# Power.net
KiCad netlist of a schematic drawn in Altium Designer
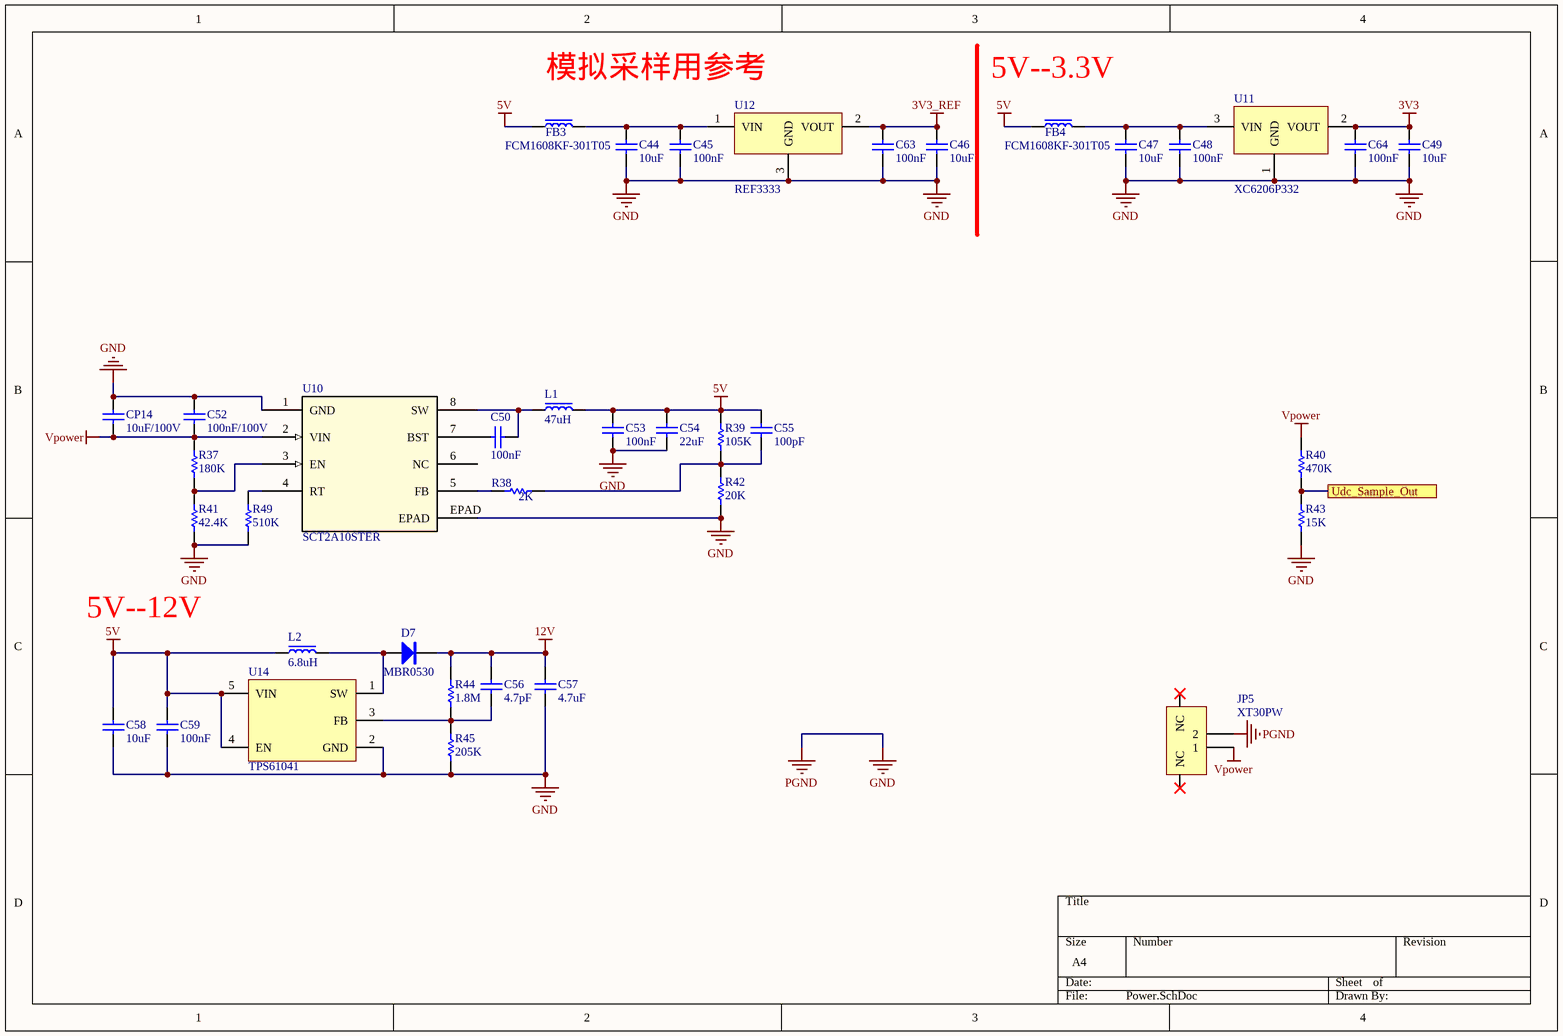
[diagram p0: Power.SchDoc]

(export (version "E")
  (design (tool "Eeschema 10.0.6"))
  (components
    (comp (ref "C44") (value "10uF") (footprint "C0603") (libsource (lib "Cap") (part "Cap")))
    (comp (ref "C45") (value "100nF") (footprint "C0603") (libsource (lib "Cap") (part "Cap")))
    (comp (ref "C46") (value "10uF") (footprint "C0603") (libsource (lib "Cap") (part "Cap")))
    (comp (ref "C47") (value "10uF") (footprint "C0603") (libsource (lib "Cap") (part "Cap")))
    (comp (ref "C48") (value "100nF") (footprint "C0603") (libsource (lib "Cap") (part "Cap")))
    (comp (ref "C49") (value "10uF") (footprint "C0603") (libsource (lib "Cap") (part "Cap")))
    (comp (ref "C50") (value "100nF") (footprint "C0603") (libsource (lib "Cap") (part "Cap")))
    (comp (ref "C52") (value "100nF/100V") (footprint "C0603") (libsource (lib "Cap") (part "Cap")))
    (comp (ref "C53") (value "100nF") (footprint "C0603") (libsource (lib "Cap") (part "Cap")))
    (comp (ref "C54") (value "22uF") (footprint "C0805") (libsource (lib "Cap") (part "Cap")))
    (comp (ref "C55") (value "100pF") (footprint "C0603") (libsource (lib "Cap") (part "Cap")))
    (comp (ref "C56") (value "4.7pF") (footprint "C0603") (libsource (lib "Cap") (part "Cap")))
    (comp (ref "C57") (value "4.7uF") (footprint "C0805") (libsource (lib "Cap") (part "Cap")))
    (comp (ref "C58") (value "10uF") (footprint "C0805") (libsource (lib "Cap") (part "Cap")))
    (comp (ref "C59") (value "100nF") (footprint "C0603") (libsource (lib "Cap") (part "Cap")))
    (comp (ref "C63") (value "100nF") (footprint "C0603") (libsource (lib "Cap") (part "Cap")))
    (comp (ref "C64") (value "100nF") (footprint "C0603") (libsource (lib "Cap") (part "Cap")))
    (comp (ref "CP14") (value "10uF/100V") (footprint "C1206") (libsource (lib "Cap") (part "Cap")))
    (comp (ref "D7")
      (value "MBR0530")
      (footprint "SOD-123")
      (description "30V 0.5A")
      (libsource (lib "All lib") (part "MBR0530"))
    )
    (comp (ref "FB3")
      (value "FCM1608KF-301T05")
      (footprint "FB 0402")
      (description "磁珠")
      (libsource (lib "All lib") (part "FB"))
    )
    (comp (ref "FB4")
      (value "FCM1608KF-301T05")
      (footprint "FB 0402")
      (description "磁珠")
      (libsource (lib "All lib") (part "FB"))
    )
    (comp (ref "JP5") (value "XT30PW") (footprint "XT30PW-M") (libsource (lib "All lib") (part "XT30PW")))
    (comp (ref "L1")
      (value "47uH")
      (footprint "L 0630")
      (description "功率屏蔽电感")
      (libsource (lib "All lib") (part "L-CDRH"))
    )
    (comp (ref "L2")
      (value "6.8uH")
      (footprint "L 0530")
      (description "功率屏蔽电感")
      (libsource (lib "All lib") (part "L-CDRH"))
    )
    (comp (ref "R37") (value "180K") (footprint "R0603") (libsource (lib "Res") (part "RES")))
    (comp (ref "R38") (value "2K") (footprint "R0603") (libsource (lib "Res") (part "RES")))
    (comp (ref "R39") (value "105K") (footprint "R0603") (libsource (lib "Res") (part "RES")))
    (comp (ref "R40") (value "470K") (footprint "R0402") (libsource (lib "Res") (part "RES")))
    (comp (ref "R41") (value "42.4K") (footprint "R0603") (libsource (lib "Res") (part "RES")))
    (comp (ref "R42") (value "20K") (footprint "R0603") (libsource (lib "Res") (part "RES")))
    (comp (ref "R43") (value "15K") (footprint "R0402") (libsource (lib "Res") (part "RES")))
    (comp (ref "R44") (value "1.8M") (footprint "R0603") (libsource (lib "Res") (part "RES")))
    (comp (ref "R45") (value "205K") (footprint "R0603") (libsource (lib "Res") (part "RES")))
    (comp (ref "R49") (value "510K") (footprint "R0603") (libsource (lib "Res") (part "RES")))
    (comp (ref "U10")
      (value "SCT2A10STER")
      (footprint "DDA8_3P1X2P41-L")
      (description "No Description Available")
      (libsource (lib "All lib") (part "SCT2A10STER"))
    )
    (comp (ref "U11")
      (value "XC6206P332")
      (footprint "SOT23-3L")
      (description "VIN < 6V")
      (libsource (lib "All lib") (part "XC6206"))
    )
    (comp (ref "U12")
      (value "REF3333")
      (footprint "SOT23-3L")
      (description "TI 电压基准")
      (libsource (lib "All lib") (part "REF33XX"))
    )
    (comp (ref "U14")
      (value "TPS61041")
      (footprint "SOT23-5L")
      (description "Boost DC-DC")
      (libsource (lib "All lib") (part "TPS6104x"))
    )
  )
  (nets
    (net (code "1") (name "/Udc_Sample_Out") (class "Default")
      (node (ref "R40") (pin "1") (pinfunction "1_1") (pintype "passive"))
      (node (ref "R43") (pin "2") (pinfunction "2_2") (pintype "passive"))
    )
    (net (code "2") (name "3V3") (class "Default")
      (node (ref "C49") (pin "2") (pinfunction "2_2") (pintype "passive"))
      (node (ref "C64") (pin "2") (pinfunction "2_2") (pintype "passive"))
      (node (ref "U11") (pin "2") (pinfunction "VOUT_2") (pintype "passive"))
    )
    (net (code "3") (name "3V3_REF") (class "Default")
      (node (ref "C46") (pin "2") (pinfunction "2_2") (pintype "passive"))
      (node (ref "C63") (pin "2") (pinfunction "2_2") (pintype "passive"))
      (node (ref "U12") (pin "2") (pinfunction "VOUT_2") (pintype "passive"))
    )
    (net (code "4") (name "5V") (class "Default")
      (node (ref "C53") (pin "2") (pinfunction "2_2") (pintype "passive"))
      (node (ref "C54") (pin "1") (pinfunction "1_1") (pintype "passive"))
      (node (ref "C55") (pin "1") (pinfunction "1_1") (pintype "passive"))
      (node (ref "C58") (pin "2") (pinfunction "2_2") (pintype "passive"))
      (node (ref "C59") (pin "2") (pinfunction "2_2") (pintype "passive"))
      (node (ref "FB3") (pin "1") (pinfunction "1_1") (pintype "passive"))
      (node (ref "FB4") (pin "1") (pinfunction "1_1") (pintype "passive"))
      (node (ref "L1") (pin "2") (pinfunction "2_2") (pintype "passive"))
      (node (ref "L2") (pin "1") (pinfunction "1_1") (pintype "passive"))
      (node (ref "R39") (pin "2") (pinfunction "2_2") (pintype "passive"))
      (node (ref "U14") (pin "4") (pinfunction "EN_4") (pintype "passive"))
      (node (ref "U14") (pin "5") (pinfunction "VIN_5") (pintype "passive"))
    )
    (net (code "5") (name "12V") (class "Default")
      (node (ref "C56") (pin "2") (pinfunction "2_2") (pintype "passive"))
      (node (ref "C57") (pin "2") (pinfunction "2_2") (pintype "passive"))
      (node (ref "D7") (pin "K") (pinfunction "K_K") (pintype "passive"))
      (node (ref "R44") (pin "1") (pinfunction "1_1") (pintype "passive"))
    )
    (net (code "6") (name "GND") (class "Default")
      (node (ref "C44") (pin "1") (pinfunction "1_1") (pintype "passive"))
      (node (ref "C45") (pin "1") (pinfunction "1_1") (pintype "passive"))
      (node (ref "C46") (pin "1") (pinfunction "1_1") (pintype "passive"))
      (node (ref "C47") (pin "1") (pinfunction "1_1") (pintype "passive"))
      (node (ref "C48") (pin "1") (pinfunction "1_1") (pintype "passive"))
      (node (ref "C49") (pin "1") (pinfunction "1_1") (pintype "passive"))
      (node (ref "C52") (pin "1") (pinfunction "1_1") (pintype "passive"))
      (node (ref "C53") (pin "1") (pinfunction "1_1") (pintype "passive"))
      (node (ref "C54") (pin "2") (pinfunction "2_2") (pintype "passive"))
      (node (ref "C57") (pin "1") (pinfunction "1_1") (pintype "passive"))
      (node (ref "C58") (pin "1") (pinfunction "1_1") (pintype "passive"))
      (node (ref "C59") (pin "1") (pinfunction "1_1") (pintype "passive"))
      (node (ref "C63") (pin "1") (pinfunction "1_1") (pintype "passive"))
      (node (ref "C64") (pin "1") (pinfunction "1_1") (pintype "passive"))
      (node (ref "CP14") (pin "1") (pinfunction "1_1") (pintype "passive"))
      (node (ref "JP5") (pin "2") (pinfunction "2_2") (pintype "passive"))
      (node (ref "R41") (pin "1") (pinfunction "1_1") (pintype "passive"))
      (node (ref "R42") (pin "1") (pinfunction "1_1") (pintype "passive"))
      (node (ref "R43") (pin "1") (pinfunction "1_1") (pintype "passive"))
      (node (ref "R45") (pin "2") (pinfunction "2_2") (pintype "passive"))
      (node (ref "R49") (pin "1") (pinfunction "1_1") (pintype "passive"))
      (node (ref "U10") (pin "1") (pinfunction "GND_1") (pintype "power_in"))
      (node (ref "U10") (pin "EPAD") (pinfunction "EPAD_EPAD") (pintype "passive"))
      (node (ref "U11") (pin "1") (pinfunction "GND_1") (pintype "passive"))
      (node (ref "U12") (pin "3") (pinfunction "GND_3") (pintype "passive"))
      (node (ref "U14") (pin "2") (pinfunction "GND_2") (pintype "passive"))
    )
    (net (code "7") (name "Net-(C55-Pad2)") (class "Default")
      (node (ref "C55") (pin "2") (pinfunction "2_2") (pintype "passive"))
      (node (ref "R38") (pin "1") (pinfunction "1_1") (pintype "passive"))
      (node (ref "R39") (pin "1") (pinfunction "1_1") (pintype "passive"))
      (node (ref "R42") (pin "2") (pinfunction "2_2") (pintype "passive"))
    )
    (net (code "8") (name "Net-(U10-BST)") (class "Default")
      (node (ref "C50") (pin "1") (pinfunction "1_1") (pintype "passive"))
      (node (ref "U10") (pin "7") (pinfunction "BST_7") (pintype "passive"))
    )
    (net (code "9") (name "Net-(U10-EN)") (class "Default")
      (node (ref "R37") (pin "1") (pinfunction "1_1") (pintype "passive"))
      (node (ref "R41") (pin "2") (pinfunction "2_2") (pintype "passive"))
      (node (ref "U10") (pin "3") (pinfunction "EN_3") (pintype "input"))
    )
    (net (code "10") (name "Net-(U10-FB)") (class "Default")
      (node (ref "R38") (pin "2") (pinfunction "2_2") (pintype "passive"))
      (node (ref "U10") (pin "5") (pinfunction "FB_5") (pintype "passive"))
    )
    (net (code "11") (name "Net-(U10-RT)") (class "Default")
      (node (ref "R49") (pin "2") (pinfunction "2_2") (pintype "passive"))
      (node (ref "U10") (pin "4") (pinfunction "RT_4") (pintype "passive"))
    )
    (net (code "12") (name "Net-(U10-SW)") (class "Default")
      (node (ref "C50") (pin "2") (pinfunction "2_2") (pintype "passive"))
      (node (ref "L1") (pin "1") (pinfunction "1_1") (pintype "passive"))
      (node (ref "U10") (pin "8") (pinfunction "SW_8") (pintype "passive"))
    )
    (net (code "13") (name "Net-(U11-VIN)") (class "Default")
      (node (ref "C47") (pin "2") (pinfunction "2_2") (pintype "passive"))
      (node (ref "C48") (pin "2") (pinfunction "2_2") (pintype "passive"))
      (node (ref "FB4") (pin "2") (pinfunction "2_2") (pintype "passive"))
      (node (ref "U11") (pin "3") (pinfunction "VIN_3") (pintype "passive"))
    )
    (net (code "14") (name "Net-(U12-VIN)") (class "Default")
      (node (ref "C44") (pin "2") (pinfunction "2_2") (pintype "passive"))
      (node (ref "C45") (pin "2") (pinfunction "2_2") (pintype "passive"))
      (node (ref "FB3") (pin "2") (pinfunction "2_2") (pintype "passive"))
      (node (ref "U12") (pin "1") (pinfunction "VIN_1") (pintype "passive"))
    )
    (net (code "15") (name "Net-(U14-FB)") (class "Default")
      (node (ref "C56") (pin "1") (pinfunction "1_1") (pintype "passive"))
      (node (ref "R44") (pin "2") (pinfunction "2_2") (pintype "passive"))
      (node (ref "R45") (pin "1") (pinfunction "1_1") (pintype "passive"))
      (node (ref "U14") (pin "3") (pinfunction "FB_3") (pintype "passive"))
    )
    (net (code "16") (name "Net-(U14-SW)") (class "Default")
      (node (ref "D7") (pin "A") (pinfunction "A_A") (pintype "passive"))
      (node (ref "L2") (pin "2") (pinfunction "2_2") (pintype "passive"))
      (node (ref "U14") (pin "1") (pinfunction "SW_1") (pintype "passive"))
    )
    (net (code "17") (name "Vpower") (class "Default")
      (node (ref "C52") (pin "2") (pinfunction "2_2") (pintype "passive"))
      (node (ref "CP14") (pin "2") (pinfunction "2_2") (pintype "passive"))
      (node (ref "JP5") (pin "1") (pinfunction "1_1") (pintype "passive"))
      (node (ref "R37") (pin "2") (pinfunction "2_2") (pintype "passive"))
      (node (ref "R40") (pin "2") (pinfunction "2_2") (pintype "passive"))
      (node (ref "U10") (pin "2") (pinfunction "VIN_2") (pintype "input"))
    )
    (net (code "18") (name "unconnected-(JP5-NC-Pad3)") (class "Default")
      (node (ref "JP5") (pin "3") (pinfunction "NC_3") (pintype "passive+no_connect"))
    )
    (net (code "19") (name "unconnected-(JP5-NC-Pad4)") (class "Default")
      (node (ref "JP5") (pin "4") (pinfunction "NC_4") (pintype "passive+no_connect"))
    )
    (net (code "20") (name "unconnected-(U10-NC-Pad6)") (class "Default")
      (node (ref "U10") (pin "6") (pinfunction "NC_6") (pintype "power_in"))
    )
  )
)
